# sensorBoard.net
KiCad netlist of a schematic drawn in EAGLE
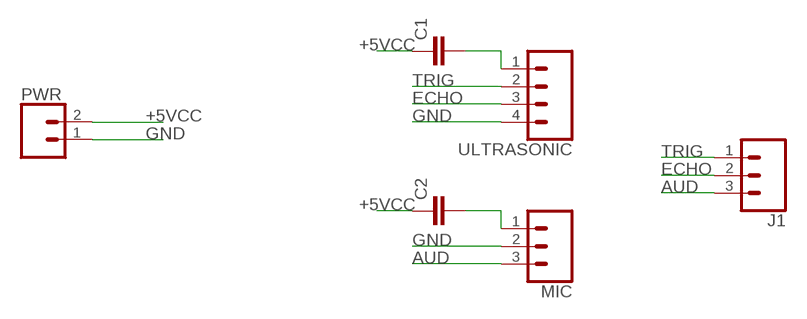
[diagram p0: schematic, sheet 1]

(export (version "E")
  (design (tool "Eeschema 10.0.6"))
  (components
    (comp (ref "C1")
      (value "C5/3")
      (footprint "eagle-import:C5B3")
      (libsource (lib "eagle-import") (part "C5/3"))
    )
    (comp (ref "C2")
      (value "C5/3")
      (footprint "eagle-import:C5B3")
      (libsource (lib "eagle-import") (part "C5/3"))
    )
    (comp (ref "J1")
      (value "CONN_03")
      (footprint "eagle-import:1X03")
      (libsource (lib "eagle-import") (part "CONN_03"))
    )
    (comp (ref "MIC")
      (value "CONN_03")
      (footprint "eagle-import:1X03")
      (libsource (lib "eagle-import") (part "CONN_03"))
    )
    (comp (ref "PWR")
      (value "CONN_02")
      (footprint "eagle-import:1X02")
      (libsource (lib "eagle-import") (part "CONN_02"))
    )
    (comp (ref "ULTRASONIC")
      (value "CONN_04")
      (footprint "eagle-import:1X04")
      (libsource (lib "eagle-import") (part "CONN_04"))
    )
  )
  (nets
    (net (code "1") (name "/+5VCC") (class "Default")
      (node (ref "C1") (pin "1") (pinfunction "1_1") (pintype "passive"))
      (node (ref "C2") (pin "1") (pinfunction "1_1") (pintype "passive"))
      (node (ref "PWR") (pin "2") (pinfunction "2_2") (pintype "passive"))
    )
    (net (code "2") (name "/AUD") (class "Default")
      (node (ref "J1") (pin "3") (pinfunction "3_3") (pintype "passive"))
      (node (ref "MIC") (pin "3") (pinfunction "3_3") (pintype "passive"))
    )
    (net (code "3") (name "/ECHO") (class "Default")
      (node (ref "J1") (pin "2") (pinfunction "2_2") (pintype "passive"))
      (node (ref "ULTRASONIC") (pin "3") (pinfunction "3_3") (pintype "passive"))
    )
    (net (code "4") (name "/GND") (class "Default")
      (node (ref "MIC") (pin "2") (pinfunction "2_2") (pintype "passive"))
      (node (ref "PWR") (pin "1") (pinfunction "1_1") (pintype "passive"))
      (node (ref "ULTRASONIC") (pin "4") (pinfunction "4_4") (pintype "passive"))
    )
    (net (code "5") (name "/TRIG") (class "Default")
      (node (ref "J1") (pin "1") (pinfunction "1_1") (pintype "passive"))
      (node (ref "ULTRASONIC") (pin "2") (pinfunction "2_2") (pintype "passive"))
    )
    (net (code "6") (name "Net-(C1-Pad2)") (class "Default")
      (node (ref "C1") (pin "2") (pinfunction "2_2") (pintype "passive"))
      (node (ref "ULTRASONIC") (pin "1") (pinfunction "1_1") (pintype "passive"))
    )
    (net (code "7") (name "Net-(C2-Pad2)") (class "Default")
      (node (ref "C2") (pin "2") (pinfunction "2_2") (pintype "passive"))
      (node (ref "MIC") (pin "1") (pinfunction "1_1") (pintype "passive"))
    )
  )
)
